# L293D.net
KiCad netlist of a schematic drawn in EAGLE
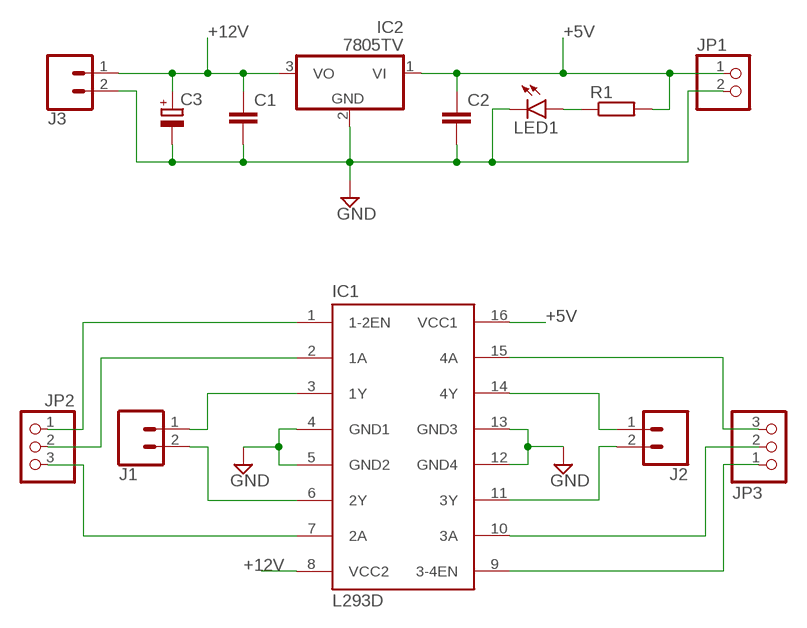
[diagram p0: schematic, sheet 1]

(export (version "E")
  (design (tool "Eeschema 10.0.6"))
  (components
    (comp (ref "C1")
      (value "C-EU025-024X044")
      (footprint "eagle-import:C025-024X044")
      (libsource (lib "eagle-import") (part "C-EU025-024X044"))
    )
    (comp (ref "C2")
      (value "C-EU025-024X044")
      (footprint "eagle-import:C025-024X044")
      (libsource (lib "eagle-import") (part "C-EU025-024X044"))
    )
    (comp (ref "C3")
      (value "CPOL-EUE2.5-5")
      (footprint "eagle-import:E2,5-5")
      (libsource (lib "eagle-import") (part "CPOL-EUE2.5-5"))
    )
    (comp (ref "IC1")
      (value "L293D")
      (footprint "eagle-import:DIL16")
      (libsource (lib "eagle-import") (part "L293D"))
    )
    (comp (ref "IC2")
      (value "7805TV")
      (footprint "eagle-import:TO220V")
      (libsource (lib "eagle-import") (part "78TV05"))
    )
    (comp (ref "J1")
      (value "CONN_025MM")
      (footprint "eagle-import:SCREWTERMINAL-5MM-2")
      (libsource (lib "eagle-import") (part "CONN_025MM"))
    )
    (comp (ref "J2")
      (value "CONN_025MM")
      (footprint "eagle-import:SCREWTERMINAL-5MM-2")
      (libsource (lib "eagle-import") (part "CONN_025MM"))
    )
    (comp (ref "J3")
      (value "CONN_025MM")
      (footprint "eagle-import:SCREWTERMINAL-5MM-2")
      (libsource (lib "eagle-import") (part "CONN_025MM"))
    )
    (comp (ref "JP1")
      (value "PINHD-1X2")
      (footprint "eagle-import:1X02")
      (libsource (lib "eagle-import") (part "PINHD-1X2"))
    )
    (comp (ref "JP2")
      (value "PINHD-1X3")
      (footprint "eagle-import:1X03")
      (libsource (lib "eagle-import") (part "PINHD-1X3"))
    )
    (comp (ref "JP3")
      (value "PINHD-1X3")
      (footprint "eagle-import:1X03")
      (libsource (lib "eagle-import") (part "PINHD-1X3"))
    )
    (comp (ref "LED1")
      (value "LED5MM")
      (footprint "eagle-import:LED5MM")
      (libsource (lib "eagle-import") (part "LED5MM"))
    )
    (comp (ref "R1")
      (value "R-EU_0204/7")
      (footprint "eagle-import:0204_7")
      (libsource (lib "eagle-import") (part "R-EU_0204/7"))
    )
  )
  (nets
    (net (code "1") (name "/+5V") (class "Default")
      (node (ref "C2") (pin "1") (pinfunction "1_1") (pintype "passive"))
      (node (ref "IC1") (pin "16") (pinfunction "VCC1_16") (pintype "power_in"))
      (node (ref "IC2") (pin "1") (pinfunction "VI_1") (pintype "input"))
      (node (ref "JP1") (pin "1") (pinfunction "1_1") (pintype "passive"))
      (node (ref "R1") (pin "2") (pinfunction "2_2") (pintype "passive"))
    )
    (net (code "2") (name "/+12V") (class "Default")
      (node (ref "C1") (pin "1") (pinfunction "1_1") (pintype "passive"))
      (node (ref "C3") (pin "+") (pinfunction "+_+") (pintype "passive"))
      (node (ref "IC1") (pin "8") (pinfunction "VCC2_8") (pintype "power_in"))
      (node (ref "IC2") (pin "3") (pinfunction "VO_3") (pintype "passive"))
      (node (ref "J3") (pin "1") (pinfunction "1_1") (pintype "passive"))
    )
    (net (code "3") (name "GND") (class "Default")
      (node (ref "C1") (pin "2") (pinfunction "2_2") (pintype "passive"))
      (node (ref "C2") (pin "2") (pinfunction "2_2") (pintype "passive"))
      (node (ref "C3") (pin "-") (pinfunction "-_-") (pintype "passive"))
      (node (ref "IC1") (pin "12") (pinfunction "GND4_12") (pintype "power_in"))
      (node (ref "IC1") (pin "13") (pinfunction "GND3_13") (pintype "power_in"))
      (node (ref "IC1") (pin "4") (pinfunction "GND1_4") (pintype "power_in"))
      (node (ref "IC1") (pin "5") (pinfunction "GND2_5") (pintype "power_in"))
      (node (ref "IC2") (pin "2") (pinfunction "GND_2") (pintype "passive"))
      (node (ref "J3") (pin "2") (pinfunction "2_2") (pintype "passive"))
      (node (ref "JP1") (pin "2") (pinfunction "2_2") (pintype "passive"))
      (node (ref "LED1") (pin "K") (pinfunction "C_K") (pintype "passive"))
    )
    (net (code "4") (name "Net-(IC1-1-2EN)") (class "Default")
      (node (ref "IC1") (pin "1") (pinfunction "1-2EN_1") (pintype "input"))
      (node (ref "JP2") (pin "1") (pinfunction "1_1") (pintype "passive"))
    )
    (net (code "5") (name "Net-(IC1-1A)") (class "Default")
      (node (ref "IC1") (pin "2") (pinfunction "1A_2") (pintype "input"))
      (node (ref "JP2") (pin "2") (pinfunction "2_2") (pintype "passive"))
    )
    (net (code "6") (name "Net-(IC1-1Y)") (class "Default")
      (node (ref "IC1") (pin "3") (pinfunction "1Y_3") (pintype "output"))
      (node (ref "J1") (pin "1") (pinfunction "1_1") (pintype "passive"))
    )
    (net (code "7") (name "Net-(IC1-2A)") (class "Default")
      (node (ref "IC1") (pin "7") (pinfunction "2A_7") (pintype "input"))
      (node (ref "JP2") (pin "3") (pinfunction "3_3") (pintype "passive"))
    )
    (net (code "8") (name "Net-(IC1-2Y)") (class "Default")
      (node (ref "IC1") (pin "6") (pinfunction "2Y_6") (pintype "output"))
      (node (ref "J1") (pin "2") (pinfunction "2_2") (pintype "passive"))
    )
    (net (code "9") (name "Net-(IC1-3-4EN)") (class "Default")
      (node (ref "IC1") (pin "9") (pinfunction "3-4EN_9") (pintype "input"))
      (node (ref "JP3") (pin "1") (pinfunction "1_1") (pintype "passive"))
    )
    (net (code "10") (name "Net-(IC1-3A)") (class "Default")
      (node (ref "IC1") (pin "10") (pinfunction "3A_10") (pintype "input"))
      (node (ref "JP3") (pin "2") (pinfunction "2_2") (pintype "passive"))
    )
    (net (code "11") (name "Net-(IC1-3Y)") (class "Default")
      (node (ref "IC1") (pin "11") (pinfunction "3Y_11") (pintype "output"))
      (node (ref "J2") (pin "2") (pinfunction "2_2") (pintype "passive"))
    )
    (net (code "12") (name "Net-(IC1-4A)") (class "Default")
      (node (ref "IC1") (pin "15") (pinfunction "4A_15") (pintype "input"))
      (node (ref "JP3") (pin "3") (pinfunction "3_3") (pintype "passive"))
    )
    (net (code "13") (name "Net-(IC1-4Y)") (class "Default")
      (node (ref "IC1") (pin "14") (pinfunction "4Y_14") (pintype "output"))
      (node (ref "J2") (pin "1") (pinfunction "1_1") (pintype "passive"))
    )
    (net (code "14") (name "Net-(LED1-PadA)") (class "Default")
      (node (ref "LED1") (pin "A") (pinfunction "A_A") (pintype "passive"))
      (node (ref "R1") (pin "1") (pinfunction "1_1") (pintype "passive"))
    )
  )
)
